# design.net
KiCad netlist of a schematic drawn in EasyEDA Pro
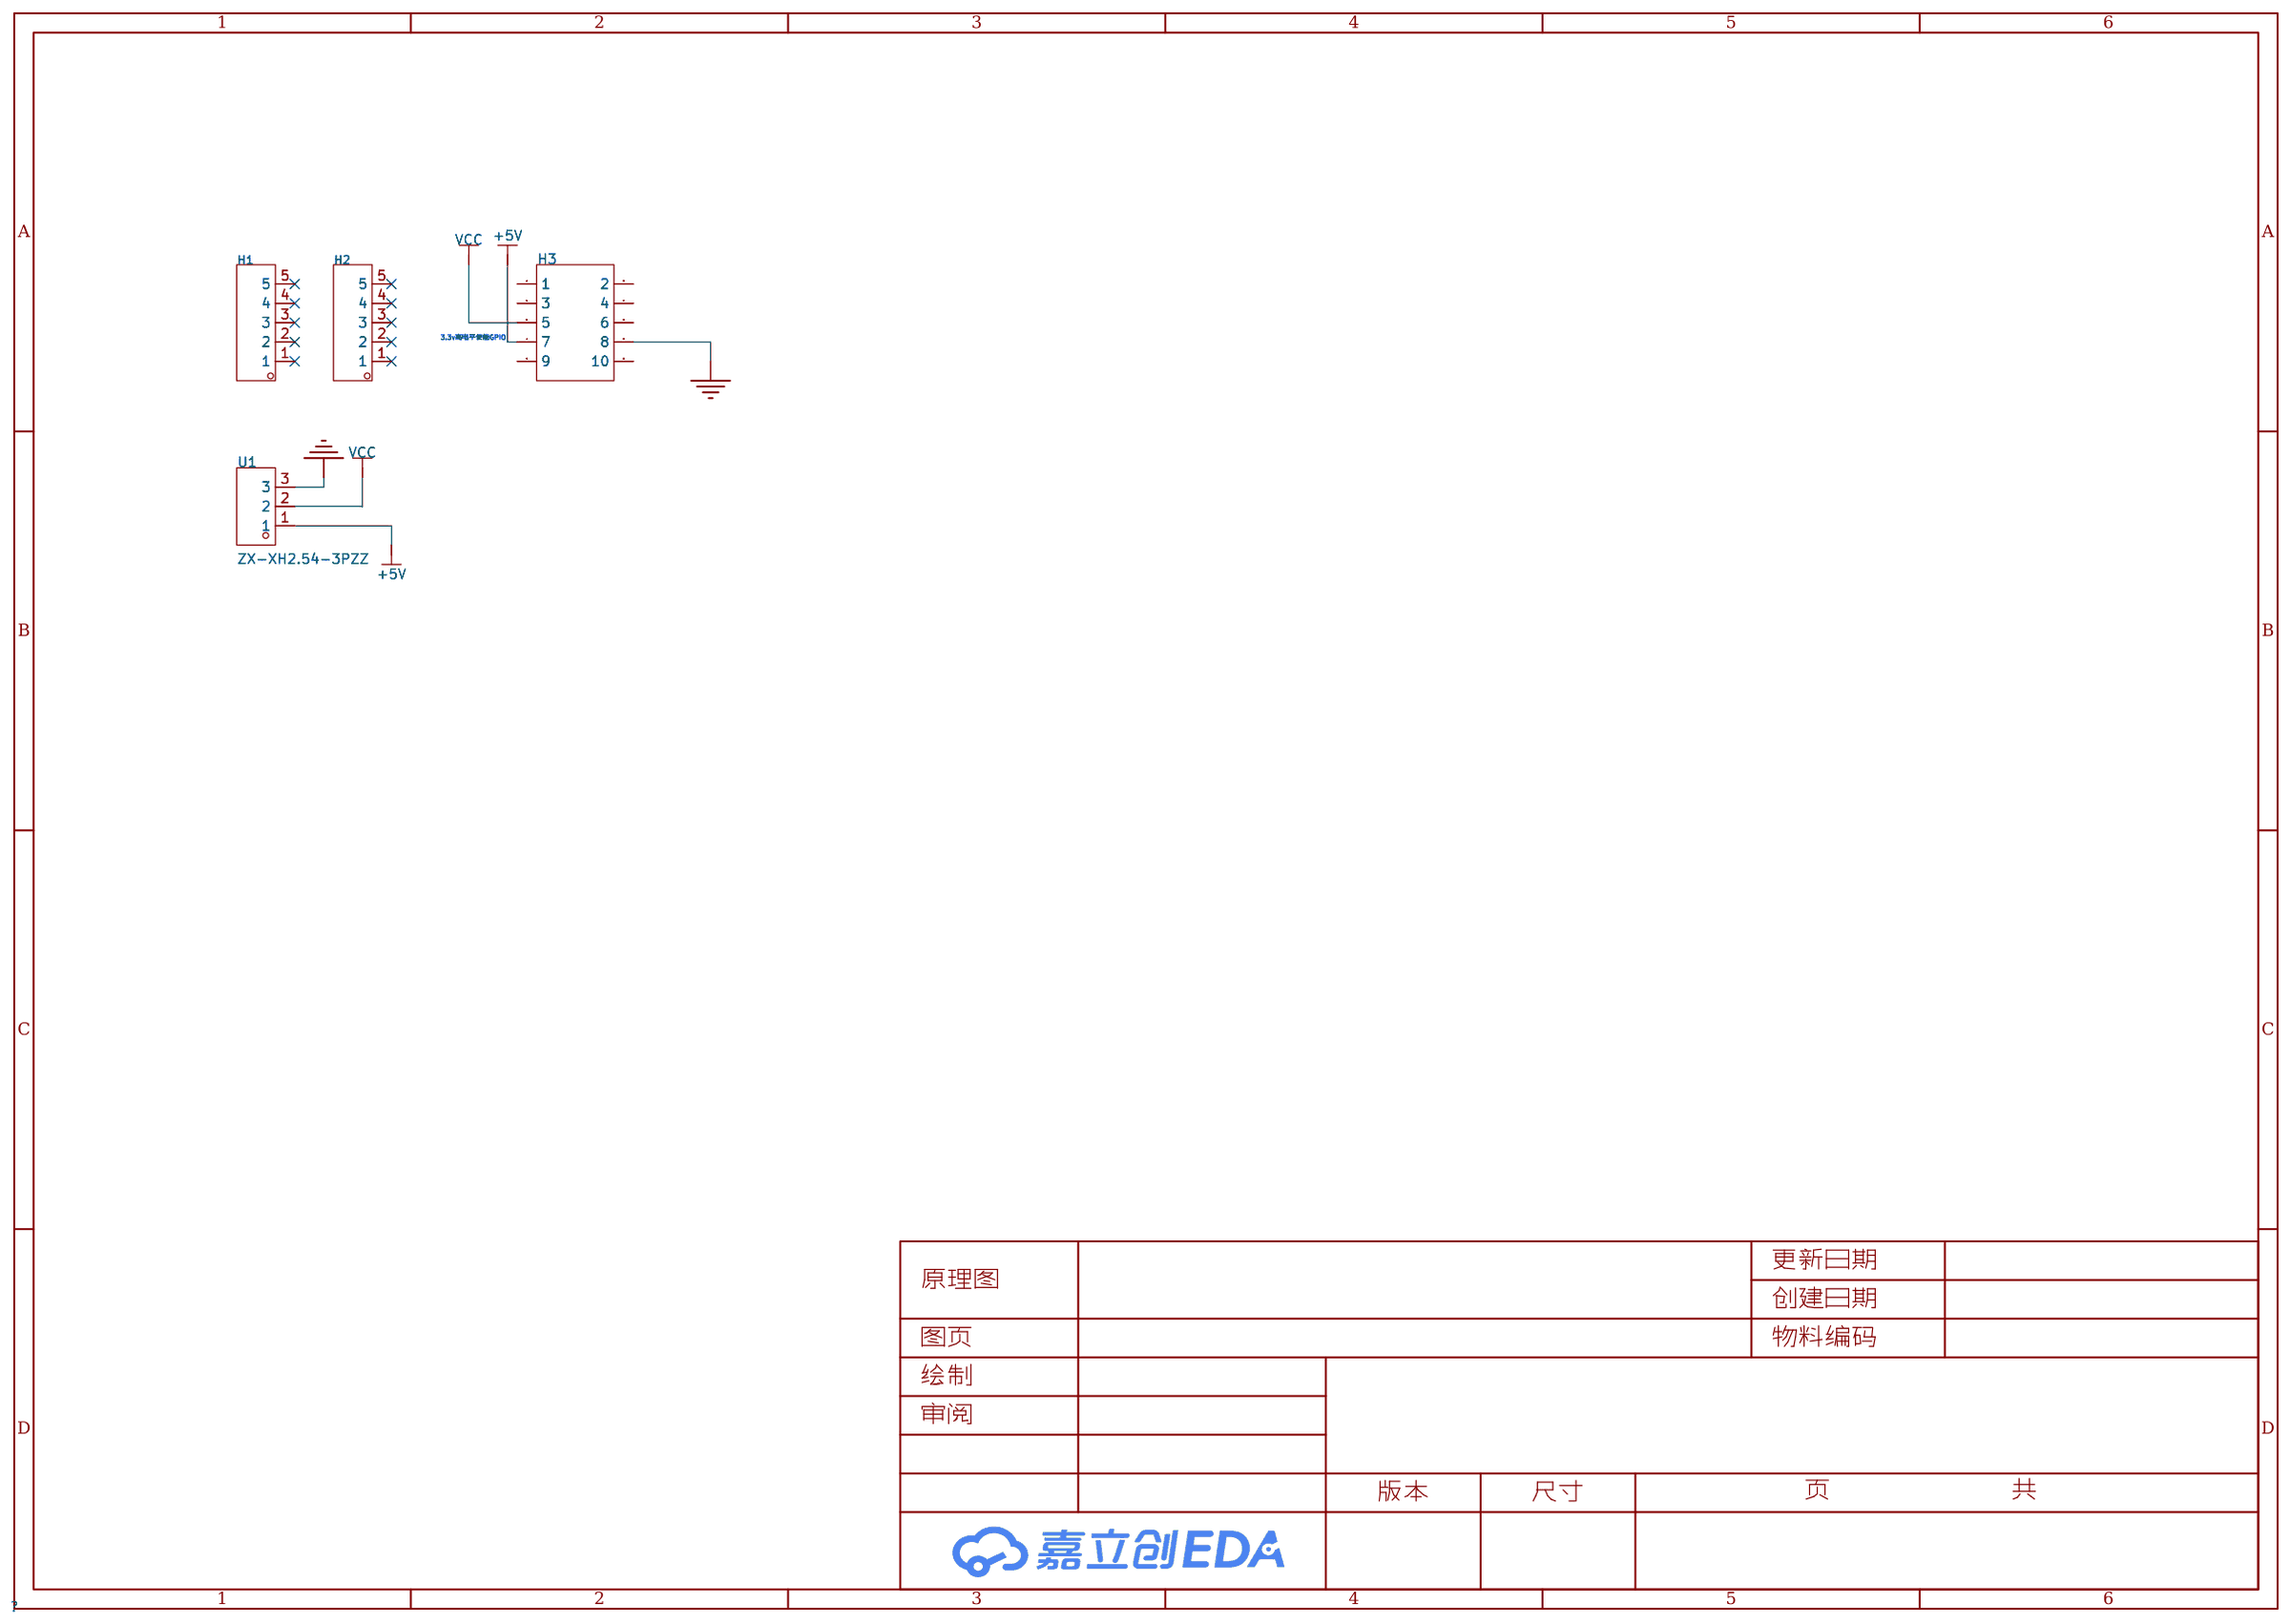
[diagram p0: schematic sheet]

(export (version "E")
  (design (tool "Eeschema 10.0.6"))
  (components
    (comp (ref "H1")
      (value "~")
      (footprint "easyedapro:HDR-TH_5P-P2.54-V-M")
      (libsource (lib "easyedapro") (part "MTP125-1105S1"))
    )
    (comp (ref "H2")
      (value "~")
      (footprint "easyedapro:HDR-TH_5P-P2.54-V-M")
      (libsource (lib "easyedapro") (part "MTP125-1105S1"))
    )
    (comp (ref "H3")
      (value "~")
      (footprint "easyedapro:HDR-TH_10P-P2.54-V-F-R2-C5-S2.54")
      (libsource (lib "easyedapro") (part "HDR-F-2.54_2x5"))
    )
    (comp (ref "U1")
      (value "ZX-XH2.54-3PZZ")
      (footprint "easyedapro:CONN-TH_3P-P2.54_2501S-3P")
      (fields (field (name "Manufacturer") "Megastar(兆星)"))
      (libsource (lib "easyedapro") (part "ZX-XH2.54-3PZZ"))
    )
  )
  (nets
    (net (code "1") (name "+5V") (class "Default")
      (node (ref "H3") (pin "7") (pinfunction "7_7") (pintype "input"))
      (node (ref "U1") (pin "1") (pinfunction "1_1") (pintype "unspecified"))
    )
    (net (code "2") (name "GND") (class "Default")
      (node (ref "H3") (pin "8") (pinfunction "8_8") (pintype "input"))
      (node (ref "U1") (pin "3") (pinfunction "3_3") (pintype "unspecified"))
    )
    (net (code "3") (name "VCC") (class "Default")
      (node (ref "H3") (pin "5") (pinfunction "5_5") (pintype "input"))
      (node (ref "U1") (pin "2") (pinfunction "2_2") (pintype "unspecified"))
    )
    (net (code "4") (name "unconnected-(H1-Pad1)") (class "Default")
      (node (ref "H1") (pin "1") (pinfunction "1_1") (pintype "input+no_connect"))
    )
    (net (code "5") (name "unconnected-(H1-Pad2)") (class "Default")
      (node (ref "H1") (pin "2") (pinfunction "2_2") (pintype "input+no_connect"))
    )
    (net (code "6") (name "unconnected-(H1-Pad3)") (class "Default")
      (node (ref "H1") (pin "3") (pinfunction "3_3") (pintype "input+no_connect"))
    )
    (net (code "7") (name "unconnected-(H1-Pad4)") (class "Default")
      (node (ref "H1") (pin "4") (pinfunction "4_4") (pintype "input+no_connect"))
    )
    (net (code "8") (name "unconnected-(H1-Pad5)") (class "Default")
      (node (ref "H1") (pin "5") (pinfunction "5_5") (pintype "input+no_connect"))
    )
    (net (code "9") (name "unconnected-(H2-Pad1)") (class "Default")
      (node (ref "H2") (pin "1") (pinfunction "1_1") (pintype "input+no_connect"))
    )
    (net (code "10") (name "unconnected-(H2-Pad2)") (class "Default")
      (node (ref "H2") (pin "2") (pinfunction "2_2") (pintype "input+no_connect"))
    )
    (net (code "11") (name "unconnected-(H2-Pad3)") (class "Default")
      (node (ref "H2") (pin "3") (pinfunction "3_3") (pintype "input+no_connect"))
    )
    (net (code "12") (name "unconnected-(H2-Pad4)") (class "Default")
      (node (ref "H2") (pin "4") (pinfunction "4_4") (pintype "input+no_connect"))
    )
    (net (code "13") (name "unconnected-(H2-Pad5)") (class "Default")
      (node (ref "H2") (pin "5") (pinfunction "5_5") (pintype "input+no_connect"))
    )
    (net (code "14") (name "unconnected-(H3-Pad1)") (class "Default")
      (node (ref "H3") (pin "1") (pinfunction "1_1") (pintype "input"))
    )
    (net (code "15") (name "unconnected-(H3-Pad2)") (class "Default")
      (node (ref "H3") (pin "2") (pinfunction "2_2") (pintype "input"))
    )
    (net (code "16") (name "unconnected-(H3-Pad3)") (class "Default")
      (node (ref "H3") (pin "3") (pinfunction "3_3") (pintype "input"))
    )
    (net (code "17") (name "unconnected-(H3-Pad4)") (class "Default")
      (node (ref "H3") (pin "4") (pinfunction "4_4") (pintype "input"))
    )
    (net (code "18") (name "unconnected-(H3-Pad6)") (class "Default")
      (node (ref "H3") (pin "6") (pinfunction "6_6") (pintype "input"))
    )
    (net (code "19") (name "unconnected-(H3-Pad9)") (class "Default")
      (node (ref "H3") (pin "9") (pinfunction "9_9") (pintype "input"))
    )
    (net (code "20") (name "unconnected-(H3-Pad10)") (class "Default")
      (node (ref "H3") (pin "10") (pinfunction "10_10") (pintype "input"))
    )
  )
)
